# Shield.net
KiCad netlist of a schematic drawn in Altium Designer
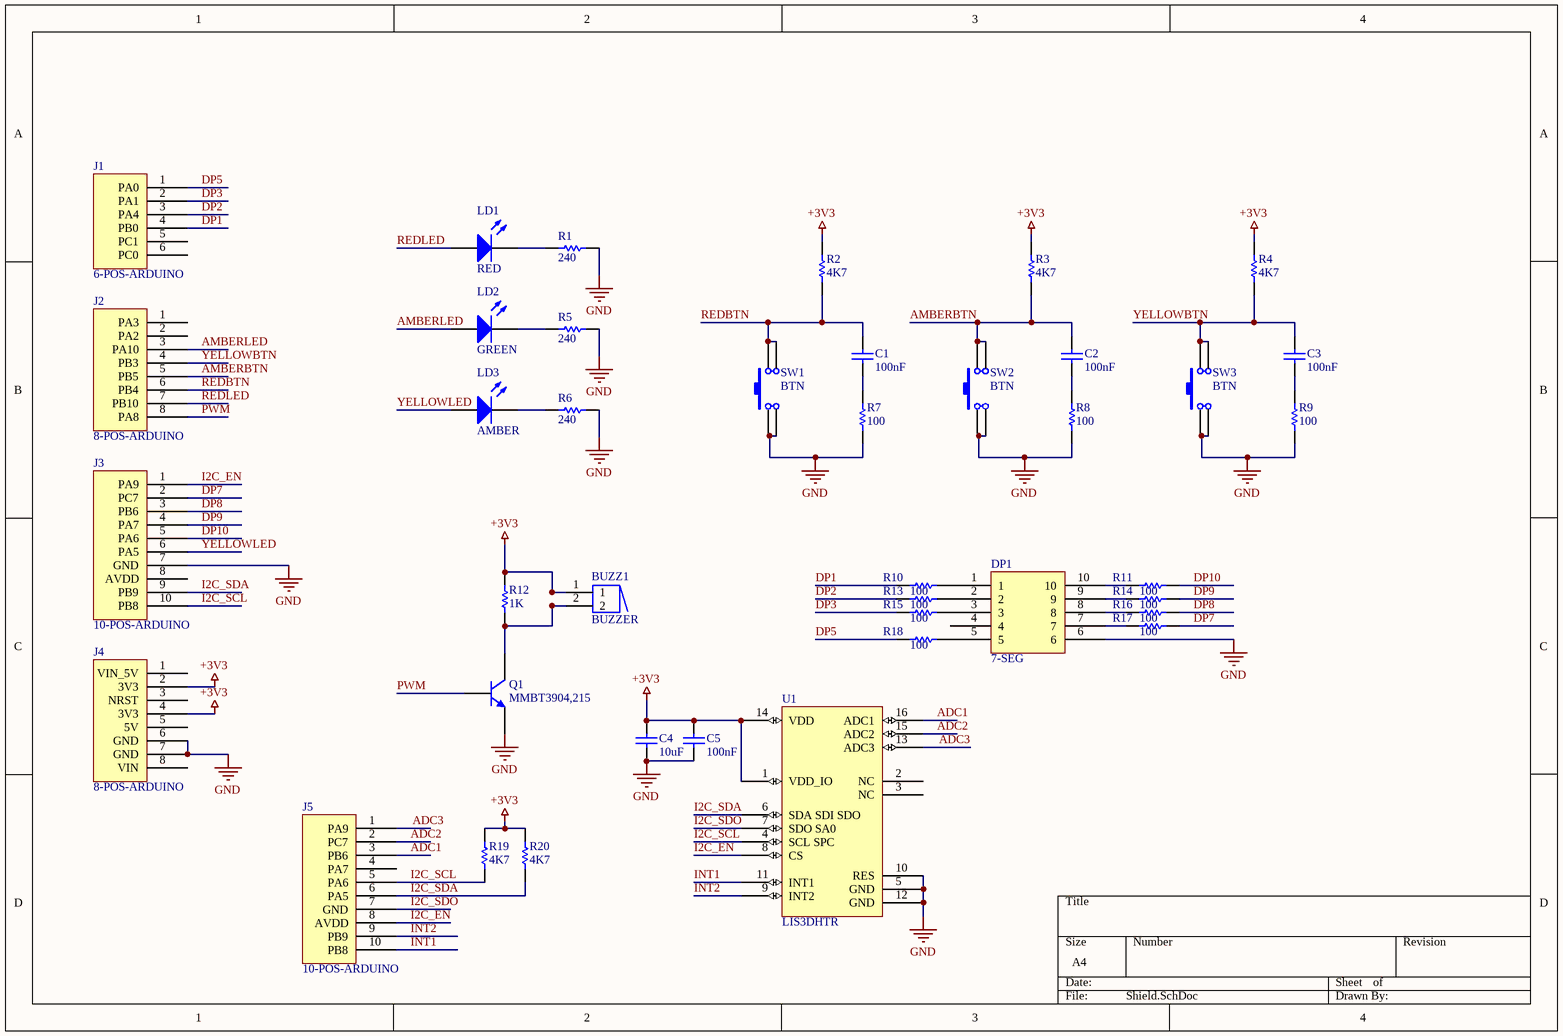
[diagram p0: Shield.SchDoc]

(export (version "E")
  (design (tool "Eeschema 10.0.6"))
  (components
    (comp (ref "BUZZ1")
      (value "BUZZER")
      (footprint "Buzzer")
      (description "AUDIO PIEZO TRANSDUCER 30V TH")
      (fields (field (name "MANUFACTURER") "TDK") (field (name "MANUFACTURER PART NUMBER") "PS1240P02BT"))
      (libsource (lib "Shield") (part "PS1240P02BT"))
    )
    (comp (ref "C1")
      (value "100nF")
      (footprint "CAPC3216X12N")
      (description "CAP CER 0.1UF 50V X7R 1206")
      (fields
        (field (name "MANUFACTURER") "Yageo")
        (field (name "MANUFACTURER PART NUMBER") "CC1206KRX7R9BB104")
      )
      (libsource (lib "Shield") (part "CC1206KRX7R9BB104"))
    )
    (comp (ref "C2")
      (value "100nF")
      (footprint "CAPC3216X12N")
      (description "CAP CER 0.1UF 50V X7R 1206")
      (fields
        (field (name "MANUFACTURER") "Yageo")
        (field (name "MANUFACTURER PART NUMBER") "CC1206KRX7R9BB104")
      )
      (libsource (lib "Shield") (part "CC1206KRX7R9BB104"))
    )
    (comp (ref "C3")
      (value "100nF")
      (footprint "CAPC3216X12N")
      (description "CAP CER 0.1UF 50V X7R 1206")
      (fields
        (field (name "MANUFACTURER") "Yageo")
        (field (name "MANUFACTURER PART NUMBER") "CC1206KRX7R9BB104")
      )
      (libsource (lib "Shield") (part "CC1206KRX7R9BB104"))
    )
    (comp (ref "C4")
      (value "10uF")
      (footprint "CAPC3216X12N")
      (description "Cap Ceramic 10uF 10V X5R 10% SMD 0805 85C Embossed T/R")
      (fields (field (name "TOLERANCE") "10%") (field (name "VOLTAGE") "10V"))
      (libsource (lib "Shield") (part "CL21A106KPFNNNG"))
    )
    (comp (ref "C5")
      (value "100nF")
      (footprint "CAPC3216X12N")
      (description "CAP CER 0.1UF 50V X7R 1206")
      (fields
        (field (name "MANUFACTURER") "Yageo")
        (field (name "MANUFACTURER PART NUMBER") "CC1206KRX7R9BB104")
      )
      (libsource (lib "Shield") (part "CC1206KRX7R9BB104"))
    )
    (comp (ref "DP1")
      (value "7-SEG")
      (footprint "7-seg-display")
      (fields
        (field (name "MANUFACTURER") "Inolux")
        (field (name "MANUFACTURER PART NUMBER") "INND-TS40YGCB")
      )
      (libsource (lib "Shield") (part "INND-TS40YGCB"))
    )
    (comp (ref "J1")
      (value "6-POS-ARDUINO")
      (footprint "PIN 6")
      (description "Conn Header Vert 6POS 2.54MM")
      (fields
        (field (name "MANUFACTURER") "Sullins")
        (field (name "MANUFACTURER PART NUMBER") "PREC006SABN-RC")
      )
      (libsource (lib "Shield") (part "PREC006SABN-RC"))
    )
    (comp (ref "J2")
      (value "8-POS-ARDUINO")
      (footprint "PIN 8")
      (description "CONN HEADER VERT 8POS 2.54MM")
      (fields
        (field (name "MANUFACTURER") "Sullins")
        (field (name "MANUFACTURER PART NUMBER") "PREC008SAAN-RC")
      )
      (libsource (lib "Shield") (part "PREC008SAAN-RC"))
    )
    (comp (ref "J3")
      (value "10-POS-ARDUINO")
      (footprint "PIN 10")
      (description "CONN HEADER .100\" SNGL STR 10POS")
      (fields
        (field (name "MANUFACTURER") "Sullins")
        (field (name "MANUFACTURER PART NUMBER") "PREC010SAAN-RC")
      )
      (libsource (lib "Shield") (part "PREC010SAAN-RC"))
    )
    (comp (ref "J4")
      (value "8-POS-ARDUINO")
      (footprint "PIN 8")
      (description "CONN HEADER VERT 8POS 2.54MM")
      (fields
        (field (name "MANUFACTURER") "Sullins")
        (field (name "MANUFACTURER PART NUMBER") "PREC008SAAN-RC")
      )
      (libsource (lib "Shield") (part "PREC008SAAN-RC (2)"))
    )
    (comp (ref "J5")
      (value "10-POS-ARDUINO")
      (footprint "PIN 10")
      (description "CONN HEADER .100\" SNGL STR 10POS")
      (fields
        (field (name "MANUFACTURER") "Sullins")
        (field (name "MANUFACTURER PART NUMBER") "PREC010SAAN-RC")
      )
      (libsource (lib "Shield") (part "PREC010SAAN-RC"))
    )
    (comp (ref "LD1")
      (value "RED")
      (footprint "DIOC3216X21N")
      (description "LED Uni-Color Red 660nm 2-Pin Chip LED T/R")
      (fields
        (field (name "MANUFACTURER") "Vishay Lite-On")
        (field (name "MANUFACTURER PART NUMBER") "LTST-C150CKT")
      )
      (libsource (lib "Shield") (part "LTST-C150CKT"))
    )
    (comp (ref "LD2")
      (value "GREEN")
      (footprint "DIOC3216X21N")
      (description "LED GREEN CLEAR 1206 SMD")
      (fields
        (field (name "MANUFACTURER") "Vishay Lite-On")
        (field (name "MANUFACTURER PART NUMBER") "LTST-C150GKT")
      )
      (libsource (lib "Shield") (part "LTST-C150GKT"))
    )
    (comp (ref "LD3")
      (value "AMBER")
      (footprint "DIOC3216X21N")
      (description "LED AMBER CLEAR 1206 SMD")
      (fields
        (field (name "MANUFACTURER") "Vishay Lite-On")
        (field (name "MANUFACTURER PART NUMBER") "LTST-C150AKT")
      )
      (libsource (lib "Shield") (part "LTST-C150AKT"))
    )
    (comp (ref "Q1")
      (value "MMBT3904,215")
      (footprint "SOT95P230X110-3N")
      (description "TRANS NPN 40V 0.2A SOT23")
      (fields (field (name "MANUFACTURER") "Nexperia"))
      (libsource (lib "Shield") (part "MMBT3904,215"))
    )
    (comp (ref "R1")
      (value "240")
      (footprint "RESC3115X06N")
      (description "Res Thick Film 1206 240 Ohm 1% 0.25W(1/4W) ±100ppm/C Molded SMD Automotive T/R")
      (fields
        (field (name "MANUFACTURER") "Stackpole Electronics")
        (field (name "MANUFACTURER PART NUMBER") "RMCF1206FT240R")
      )
      (libsource (lib "Shield") (part "RMCF1206FT240R"))
    )
    (comp (ref "R2")
      (value "4K7")
      (footprint "RESC3115X06N")
      (description "RES SMD 4.7K OHM 1% 1/4W 1206")
      (fields
        (field (name "MANUFACTURER") "Stackpole Electronics")
        (field (name "MANUFACTURER PART NUMBER") "RMCF1206FT4K70")
      )
      (libsource (lib "Shield") (part "RMCF1206FT4K70"))
    )
    (comp (ref "R3")
      (value "4K7")
      (footprint "RESC3115X06N")
      (description "RES SMD 4.7K OHM 1% 1/4W 1206")
      (fields
        (field (name "MANUFACTURER") "Stackpole Electronics")
        (field (name "MANUFACTURER PART NUMBER") "RMCF1206FT4K70")
      )
      (libsource (lib "Shield") (part "RMCF1206FT4K70"))
    )
    (comp (ref "R4")
      (value "4K7")
      (footprint "RESC3115X06N")
      (description "RES SMD 4.7K OHM 1% 1/4W 1206")
      (fields
        (field (name "MANUFACTURER") "Stackpole Electronics")
        (field (name "MANUFACTURER PART NUMBER") "RMCF1206FT4K70")
      )
      (libsource (lib "Shield") (part "RMCF1206FT4K70"))
    )
    (comp (ref "R5")
      (value "240")
      (footprint "RESC3115X06N")
      (description "Res Thick Film 1206 240 Ohm 1% 0.25W(1/4W) ±100ppm/C Molded SMD Automotive T/R")
      (fields
        (field (name "MANUFACTURER") "Stackpole Electronics")
        (field (name "MANUFACTURER PART NUMBER") "RMCF1206FT240R")
      )
      (libsource (lib "Shield") (part "RMCF1206FT240R"))
    )
    (comp (ref "R6")
      (value "240")
      (footprint "RESC3115X06N")
      (description "Res Thick Film 1206 240 Ohm 1% 0.25W(1/4W) ±100ppm/C Molded SMD Automotive T/R")
      (fields
        (field (name "MANUFACTURER") "Stackpole Electronics")
        (field (name "MANUFACTURER PART NUMBER") "RMCF1206FT240R")
      )
      (libsource (lib "Shield") (part "RMCF1206FT240R"))
    )
    (comp (ref "R7")
      (value "100")
      (footprint "RESC3115X06N")
      (description "RES 100 OHM 1% 1/4W 1206")
      (fields
        (field (name "MANUFACTURER") "Stackpole Electronics")
        (field (name "MANUFACTURER PART NUMBER") "RMCF1206FT100R")
      )
      (libsource (lib "Shield") (part "RMCF1206FT100R"))
    )
    (comp (ref "R8")
      (value "100")
      (footprint "RESC3115X06N")
      (description "RES 100 OHM 1% 1/4W 1206")
      (fields
        (field (name "MANUFACTURER") "Stackpole Electronics")
        (field (name "MANUFACTURER PART NUMBER") "RMCF1206FT100R")
      )
      (libsource (lib "Shield") (part "RMCF1206FT100R"))
    )
    (comp (ref "R9")
      (value "100")
      (footprint "RESC3115X06N")
      (description "RES 100 OHM 1% 1/4W 1206")
      (fields
        (field (name "MANUFACTURER") "Stackpole Electronics")
        (field (name "MANUFACTURER PART NUMBER") "RMCF1206FT100R")
      )
      (libsource (lib "Shield") (part "RMCF1206FT100R"))
    )
    (comp (ref "R10")
      (value "100")
      (footprint "RESC3115X06N")
      (description "RES 100 OHM 1% 1/4W 1206")
      (fields
        (field (name "MANUFACTURER") "Stackpole Electronics")
        (field (name "MANUFACTURER PART NUMBER") "RMCF1206FT100R")
      )
      (libsource (lib "Shield") (part "RMCF1206FT100R"))
    )
    (comp (ref "R11")
      (value "100")
      (footprint "RESC3115X06N")
      (description "RES 100 OHM 1% 1/4W 1206")
      (fields
        (field (name "MANUFACTURER") "Stackpole Electronics")
        (field (name "MANUFACTURER PART NUMBER") "RMCF1206FT100R")
      )
      (libsource (lib "Shield") (part "RMCF1206FT100R"))
    )
    (comp (ref "R12")
      (value "1K")
      (footprint "RESC3115X06N")
      (description "RES 1K OHM 1% 1/2W 1206")
      (fields
        (field (name "MANUFACTURER") "Stackpole Electronics")
        (field (name "MANUFACTURER PART NUMBER") "RNCP1206FTD1K00")
      )
      (libsource (lib "Shield") (part "RNCP1206FTD1K00"))
    )
    (comp (ref "R13")
      (value "100")
      (footprint "RESC3115X06N")
      (description "RES 100 OHM 1% 1/4W 1206")
      (fields
        (field (name "MANUFACTURER") "Stackpole Electronics")
        (field (name "MANUFACTURER PART NUMBER") "RMCF1206FT100R")
      )
      (libsource (lib "Shield") (part "RMCF1206FT100R"))
    )
    (comp (ref "R14")
      (value "100")
      (footprint "RESC3115X06N")
      (description "RES 100 OHM 1% 1/4W 1206")
      (fields
        (field (name "MANUFACTURER") "Stackpole Electronics")
        (field (name "MANUFACTURER PART NUMBER") "RMCF1206FT100R")
      )
      (libsource (lib "Shield") (part "RMCF1206FT100R"))
    )
    (comp (ref "R15")
      (value "100")
      (footprint "RESC3115X06N")
      (description "RES 100 OHM 1% 1/4W 1206")
      (fields
        (field (name "MANUFACTURER") "Stackpole Electronics")
        (field (name "MANUFACTURER PART NUMBER") "RMCF1206FT100R")
      )
      (libsource (lib "Shield") (part "RMCF1206FT100R"))
    )
    (comp (ref "R16")
      (value "100")
      (footprint "RESC3115X06N")
      (description "RES 100 OHM 1% 1/4W 1206")
      (fields
        (field (name "MANUFACTURER") "Stackpole Electronics")
        (field (name "MANUFACTURER PART NUMBER") "RMCF1206FT100R")
      )
      (libsource (lib "Shield") (part "RMCF1206FT100R"))
    )
    (comp (ref "R17")
      (value "100")
      (footprint "RESC3115X06N")
      (description "RES 100 OHM 1% 1/4W 1206")
      (fields
        (field (name "MANUFACTURER") "Stackpole Electronics")
        (field (name "MANUFACTURER PART NUMBER") "RMCF1206FT100R")
      )
      (libsource (lib "Shield") (part "RMCF1206FT100R"))
    )
    (comp (ref "R18")
      (value "100")
      (footprint "RESC3115X06N")
      (description "RES 100 OHM 1% 1/4W 1206")
      (fields
        (field (name "MANUFACTURER") "Stackpole Electronics")
        (field (name "MANUFACTURER PART NUMBER") "RMCF1206FT100R")
      )
      (libsource (lib "Shield") (part "RMCF1206FT100R"))
    )
    (comp (ref "R19")
      (value "4K7")
      (footprint "RESC3115X06N")
      (description "RES SMD 4.7K OHM 1% 1/4W 1206")
      (fields
        (field (name "MANUFACTURER") "Stackpole Electronics")
        (field (name "MANUFACTURER PART NUMBER") "RMCF1206FT4K70")
      )
      (libsource (lib "Shield") (part "RMCF1206FT4K70"))
    )
    (comp (ref "R20")
      (value "4K7")
      (footprint "RESC3115X06N")
      (description "RES SMD 4.7K OHM 1% 1/4W 1206")
      (fields
        (field (name "MANUFACTURER") "Stackpole Electronics")
        (field (name "MANUFACTURER PART NUMBER") "RMCF1206FT4K70")
      )
      (libsource (lib "Shield") (part "RMCF1206FT4K70"))
    )
    (comp (ref "SW1")
      (value "BTN")
      (footprint "Button")
      (description "INWALL LENS COVER , WHITE , 6 (")
      (fields
        (field (name "MANUFACTURER") "ITT C&K")
        (field (name "MANUFACTURER PART NUMBER") "PTS647SK70SMTR2LFS")
      )
      (libsource (lib "Shield") (part "PTS647SK70SMTR2LFS"))
    )
    (comp (ref "SW2")
      (value "BTN")
      (footprint "Button")
      (description "INWALL LENS COVER , WHITE , 6 (")
      (fields
        (field (name "MANUFACTURER") "ITT C&K")
        (field (name "MANUFACTURER PART NUMBER") "PTS647SK70SMTR2LFS")
      )
      (libsource (lib "Shield") (part "PTS647SK70SMTR2LFS"))
    )
    (comp (ref "SW3")
      (value "BTN")
      (footprint "Button")
      (description "INWALL LENS COVER , WHITE , 6 (")
      (fields
        (field (name "MANUFACTURER") "ITT C&K")
        (field (name "MANUFACTURER PART NUMBER") "PTS647SK70SMTR2LFS")
      )
      (libsource (lib "Shield") (part "PTS647SK70SMTR2LFS"))
    )
    (comp (ref "U1")
      (value "LIS3DHTR")
      (footprint "LGA16")
      (description "ACCEL 2-16G I2C/SPI 16LGA")
      (libsource (lib "Shield") (part "LIS3DHTR"))
    )
  )
  (nets
    (net (code "1") (name "+3V3") (class "Default")
      (node (ref "BUZZ1") (pin "1") (pinfunction "1_1") (pintype "passive"))
      (node (ref "C4") (pin "2") (pinfunction "2_2") (pintype "passive"))
      (node (ref "C5") (pin "2") (pinfunction "2_2") (pintype "passive"))
      (node (ref "J4") (pin "2") (pinfunction "3V3_2") (pintype "passive"))
      (node (ref "J4") (pin "4") (pinfunction "3V3_4") (pintype "passive"))
      (node (ref "R12") (pin "2") (pinfunction "2_2") (pintype "passive"))
      (node (ref "R19") (pin "2") (pinfunction "2_2") (pintype "passive"))
      (node (ref "R2") (pin "2") (pinfunction "2_2") (pintype "passive"))
      (node (ref "R20") (pin "2") (pinfunction "2_2") (pintype "passive"))
      (node (ref "R3") (pin "2") (pinfunction "2_2") (pintype "passive"))
      (node (ref "R4") (pin "2") (pinfunction "2_2") (pintype "passive"))
      (node (ref "U1") (pin "1") (pinfunction "VDD_IO_1") (pintype "bidirectional"))
      (node (ref "U1") (pin "14") (pinfunction "VDD_14") (pintype "bidirectional"))
    )
    (net (code "2") (name "/ADC1") (class "Default")
      (node (ref "J5") (pin "3") (pinfunction "PB6_3") (pintype "passive"))
      (node (ref "U1") (pin "16") (pinfunction "ADC1_16") (pintype "bidirectional"))
    )
    (net (code "3") (name "/ADC2") (class "Default")
      (node (ref "J5") (pin "2") (pinfunction "PC7_2") (pintype "passive"))
      (node (ref "U1") (pin "15") (pinfunction "ADC2_15") (pintype "bidirectional"))
    )
    (net (code "4") (name "/ADC3") (class "Default")
      (node (ref "J5") (pin "1") (pinfunction "PA9_1") (pintype "passive"))
      (node (ref "U1") (pin "13") (pinfunction "ADC3_13") (pintype "bidirectional"))
    )
    (net (code "5") (name "/AMBERBTN") (class "Default")
      (node (ref "C2") (pin "2") (pinfunction "2_2") (pintype "passive"))
      (node (ref "J2") (pin "5") (pinfunction "PB5_5") (pintype "passive"))
      (node (ref "R3") (pin "1") (pinfunction "1_1") (pintype "passive"))
      (node (ref "SW2") (pin "3") (pinfunction "2_3") (pintype "passive"))
      (node (ref "SW2") (pin "4") (pinfunction "3_4") (pintype "passive"))
    )
    (net (code "6") (name "/AMBERLED") (class "Default")
      (node (ref "J2") (pin "3") (pinfunction "PA10_3") (pintype "passive"))
      (node (ref "LD2") (pin "1") (pinfunction "A_1") (pintype "passive"))
    )
    (net (code "7") (name "/DP1") (class "Default")
      (node (ref "J1") (pin "4") (pinfunction "PB0_4") (pintype "passive"))
      (node (ref "R10") (pin "2") (pinfunction "2_2") (pintype "passive"))
    )
    (net (code "8") (name "/DP2") (class "Default")
      (node (ref "J1") (pin "3") (pinfunction "PA4_3") (pintype "passive"))
      (node (ref "R13") (pin "2") (pinfunction "2_2") (pintype "passive"))
    )
    (net (code "9") (name "/DP3") (class "Default")
      (node (ref "J1") (pin "2") (pinfunction "PA1_2") (pintype "passive"))
      (node (ref "R15") (pin "2") (pinfunction "2_2") (pintype "passive"))
    )
    (net (code "10") (name "/DP5") (class "Default")
      (node (ref "J1") (pin "1") (pinfunction "PA0_1") (pintype "passive"))
      (node (ref "R18") (pin "2") (pinfunction "2_2") (pintype "passive"))
    )
    (net (code "11") (name "/DP7") (class "Default")
      (node (ref "J3") (pin "2") (pinfunction "PC7_2") (pintype "passive"))
      (node (ref "R17") (pin "1") (pinfunction "1_1") (pintype "passive"))
    )
    (net (code "12") (name "/DP8") (class "Default")
      (node (ref "J3") (pin "3") (pinfunction "PB6_3") (pintype "passive"))
      (node (ref "R16") (pin "1") (pinfunction "1_1") (pintype "passive"))
    )
    (net (code "13") (name "/DP9") (class "Default")
      (node (ref "J3") (pin "4") (pinfunction "PA7_4") (pintype "passive"))
      (node (ref "R14") (pin "1") (pinfunction "1_1") (pintype "passive"))
    )
    (net (code "14") (name "/DP10") (class "Default")
      (node (ref "J3") (pin "5") (pinfunction "PA6_5") (pintype "passive"))
      (node (ref "R11") (pin "1") (pinfunction "1_1") (pintype "passive"))
    )
    (net (code "15") (name "/I2C_EN") (class "Default")
      (node (ref "J3") (pin "1") (pinfunction "PA9_1") (pintype "passive"))
      (node (ref "J5") (pin "8") (pinfunction "AVDD_8") (pintype "passive"))
      (node (ref "U1") (pin "8") (pinfunction "CS_8") (pintype "bidirectional"))
    )
    (net (code "16") (name "/I2C_SCL") (class "Default")
      (node (ref "J3") (pin "10") (pinfunction "PB8_10") (pintype "passive"))
      (node (ref "J5") (pin "5") (pinfunction "PA6_5") (pintype "passive"))
      (node (ref "R19") (pin "1") (pinfunction "1_1") (pintype "passive"))
      (node (ref "U1") (pin "4") (pinfunction "SCL_SPC_4") (pintype "bidirectional"))
    )
    (net (code "17") (name "/I2C_SDA") (class "Default")
      (node (ref "J3") (pin "9") (pinfunction "PB9_9") (pintype "passive"))
      (node (ref "J5") (pin "6") (pinfunction "PA5_6") (pintype "passive"))
      (node (ref "R20") (pin "1") (pinfunction "1_1") (pintype "passive"))
      (node (ref "U1") (pin "6") (pinfunction "SDA_SDI_SDO_6") (pintype "bidirectional"))
    )
    (net (code "18") (name "/I2C_SDO") (class "Default")
      (node (ref "J5") (pin "7") (pinfunction "GND_7") (pintype "passive"))
      (node (ref "U1") (pin "7") (pinfunction "SDO_SA0_7") (pintype "bidirectional"))
    )
    (net (code "19") (name "/INT1") (class "Default")
      (node (ref "J5") (pin "10") (pinfunction "PB8_10") (pintype "passive"))
      (node (ref "U1") (pin "11") (pinfunction "INT1_11") (pintype "bidirectional"))
    )
    (net (code "20") (name "/INT2") (class "Default")
      (node (ref "J5") (pin "9") (pinfunction "PB9_9") (pintype "passive"))
      (node (ref "U1") (pin "9") (pinfunction "INT2_9") (pintype "bidirectional"))
    )
    (net (code "21") (name "/PWM") (class "Default")
      (node (ref "J2") (pin "8") (pinfunction "PA8_8") (pintype "passive"))
      (node (ref "Q1") (pin "1") (pinfunction "B_1") (pintype "passive"))
    )
    (net (code "22") (name "/REDBTN") (class "Default")
      (node (ref "C1") (pin "2") (pinfunction "2_2") (pintype "passive"))
      (node (ref "J2") (pin "6") (pinfunction "PB4_6") (pintype "passive"))
      (node (ref "R2") (pin "1") (pinfunction "1_1") (pintype "passive"))
      (node (ref "SW1") (pin "3") (pinfunction "2_3") (pintype "passive"))
      (node (ref "SW1") (pin "4") (pinfunction "3_4") (pintype "passive"))
    )
    (net (code "23") (name "/REDLED") (class "Default")
      (node (ref "J2") (pin "7") (pinfunction "PB10_7") (pintype "passive"))
      (node (ref "LD1") (pin "1") (pinfunction "A_1") (pintype "passive"))
    )
    (net (code "24") (name "/YELLOWBTN") (class "Default")
      (node (ref "C3") (pin "2") (pinfunction "2_2") (pintype "passive"))
      (node (ref "J2") (pin "4") (pinfunction "PB3_4") (pintype "passive"))
      (node (ref "R4") (pin "1") (pinfunction "1_1") (pintype "passive"))
      (node (ref "SW3") (pin "3") (pinfunction "2_3") (pintype "passive"))
      (node (ref "SW3") (pin "4") (pinfunction "3_4") (pintype "passive"))
    )
    (net (code "25") (name "/YELLOWLED") (class "Default")
      (node (ref "J3") (pin "6") (pinfunction "PA5_6") (pintype "passive"))
      (node (ref "LD3") (pin "1") (pinfunction "A_1") (pintype "passive"))
    )
    (net (code "26") (name "GND") (class "Default")
      (node (ref "C4") (pin "1") (pinfunction "1_1") (pintype "passive"))
      (node (ref "C5") (pin "1") (pinfunction "1_1") (pintype "passive"))
      (node (ref "DP1") (pin "6") (pinfunction "6_6") (pintype "passive"))
      (node (ref "J3") (pin "7") (pinfunction "GND_7") (pintype "passive"))
      (node (ref "J4") (pin "6") (pinfunction "GND_6") (pintype "passive"))
      (node (ref "J4") (pin "7") (pinfunction "GND_7") (pintype "passive"))
      (node (ref "Q1") (pin "2") (pinfunction "E_2") (pintype "passive"))
      (node (ref "R1") (pin "2") (pinfunction "2_2") (pintype "passive"))
      (node (ref "R5") (pin "2") (pinfunction "2_2") (pintype "passive"))
      (node (ref "R6") (pin "2") (pinfunction "2_2") (pintype "passive"))
      (node (ref "R7") (pin "1") (pinfunction "1_1") (pintype "passive"))
      (node (ref "R8") (pin "1") (pinfunction "1_1") (pintype "passive"))
      (node (ref "R9") (pin "1") (pinfunction "1_1") (pintype "passive"))
      (node (ref "SW1") (pin "1") (pinfunction "1_1") (pintype "passive"))
      (node (ref "SW1") (pin "2") (pinfunction "1_2") (pintype "passive"))
      (node (ref "SW2") (pin "1") (pinfunction "1_1") (pintype "passive"))
      (node (ref "SW2") (pin "2") (pinfunction "1_2") (pintype "passive"))
      (node (ref "SW3") (pin "1") (pinfunction "1_1") (pintype "passive"))
      (node (ref "SW3") (pin "2") (pinfunction "1_2") (pintype "passive"))
      (node (ref "U1") (pin "10") (pinfunction "RES_10") (pintype "power_in"))
      (node (ref "U1") (pin "12") (pinfunction "GND_12") (pintype "power_in"))
      (node (ref "U1") (pin "5") (pinfunction "GND_5") (pintype "power_in"))
    )
    (net (code "27") (name "Net-(C1-Pad1)") (class "Default")
      (node (ref "C1") (pin "1") (pinfunction "1_1") (pintype "passive"))
      (node (ref "R7") (pin "2") (pinfunction "2_2") (pintype "passive"))
    )
    (net (code "28") (name "Net-(C2-Pad1)") (class "Default")
      (node (ref "C2") (pin "1") (pinfunction "1_1") (pintype "passive"))
      (node (ref "R8") (pin "2") (pinfunction "2_2") (pintype "passive"))
    )
    (net (code "29") (name "Net-(C3-Pad1)") (class "Default")
      (node (ref "C3") (pin "1") (pinfunction "1_1") (pintype "passive"))
      (node (ref "R9") (pin "2") (pinfunction "2_2") (pintype "passive"))
    )
    (net (code "30") (name "Net-(DP1-Pad1)") (class "Default")
      (node (ref "DP1") (pin "1") (pinfunction "1_1") (pintype "passive"))
      (node (ref "R10") (pin "1") (pinfunction "1_1") (pintype "passive"))
    )
    (net (code "31") (name "Net-(DP1-Pad2)") (class "Default")
      (node (ref "DP1") (pin "2") (pinfunction "2_2") (pintype "passive"))
      (node (ref "R13") (pin "1") (pinfunction "1_1") (pintype "passive"))
    )
    (net (code "32") (name "Net-(DP1-Pad3)") (class "Default")
      (node (ref "DP1") (pin "3") (pinfunction "3_3") (pintype "passive"))
      (node (ref "R15") (pin "1") (pinfunction "1_1") (pintype "passive"))
    )
    (net (code "33") (name "Net-(DP1-Pad5)") (class "Default")
      (node (ref "DP1") (pin "5") (pinfunction "5_5") (pintype "passive"))
      (node (ref "R18") (pin "1") (pinfunction "1_1") (pintype "passive"))
    )
    (net (code "34") (name "Net-(DP1-Pad7)") (class "Default")
      (node (ref "DP1") (pin "7") (pinfunction "7_7") (pintype "passive"))
      (node (ref "R17") (pin "2") (pinfunction "2_2") (pintype "passive"))
    )
    (net (code "35") (name "Net-(DP1-Pad8)") (class "Default")
      (node (ref "DP1") (pin "8") (pinfunction "8_8") (pintype "passive"))
      (node (ref "R16") (pin "2") (pinfunction "2_2") (pintype "passive"))
    )
    (net (code "36") (name "Net-(DP1-Pad9)") (class "Default")
      (node (ref "DP1") (pin "9") (pinfunction "9_9") (pintype "passive"))
      (node (ref "R14") (pin "2") (pinfunction "2_2") (pintype "passive"))
    )
    (net (code "37") (name "Net-(DP1-Pad10)") (class "Default")
      (node (ref "DP1") (pin "10") (pinfunction "10_10") (pintype "passive"))
      (node (ref "R11") (pin "2") (pinfunction "2_2") (pintype "passive"))
    )
    (net (code "38") (name "Net-(LD1-K)") (class "Default")
      (node (ref "LD1") (pin "2") (pinfunction "K_2") (pintype "passive"))
      (node (ref "R1") (pin "1") (pinfunction "1_1") (pintype "passive"))
    )
    (net (code "39") (name "Net-(LD2-K)") (class "Default")
      (node (ref "LD2") (pin "2") (pinfunction "K_2") (pintype "passive"))
      (node (ref "R5") (pin "1") (pinfunction "1_1") (pintype "passive"))
    )
    (net (code "40") (name "Net-(LD3-K)") (class "Default")
      (node (ref "LD3") (pin "2") (pinfunction "K_2") (pintype "passive"))
      (node (ref "R6") (pin "1") (pinfunction "1_1") (pintype "passive"))
    )
    (net (code "41") (name "Net-(Q1-C)") (class "Default")
      (node (ref "BUZZ1") (pin "2") (pinfunction "2_2") (pintype "passive"))
      (node (ref "Q1") (pin "3") (pinfunction "C_3") (pintype "passive"))
      (node (ref "R12") (pin "1") (pinfunction "1_1") (pintype "passive"))
    )
    (net (code "42") (name "unconnected-(DP1-Pad4)") (class "Default")
      (node (ref "DP1") (pin "4") (pinfunction "4_4") (pintype "passive"))
    )
    (net (code "43") (name "unconnected-(J1-PC0-Pad6)") (class "Default")
      (node (ref "J1") (pin "6") (pinfunction "PC0_6") (pintype "passive"))
    )
    (net (code "44") (name "unconnected-(J1-PC1-Pad5)") (class "Default")
      (node (ref "J1") (pin "5") (pinfunction "PC1_5") (pintype "passive"))
    )
    (net (code "45") (name "unconnected-(J2-PA2-Pad2)") (class "Default")
      (node (ref "J2") (pin "2") (pinfunction "PA2_2") (pintype "passive"))
    )
    (net (code "46") (name "unconnected-(J2-PA3-Pad1)") (class "Default")
      (node (ref "J2") (pin "1") (pinfunction "PA3_1") (pintype "passive"))
    )
    (net (code "47") (name "unconnected-(J3-AVDD-Pad8)") (class "Default")
      (node (ref "J3") (pin "8") (pinfunction "AVDD_8") (pintype "passive"))
    )
    (net (code "48") (name "unconnected-(J4-5V-Pad5)") (class "Default")
      (node (ref "J4") (pin "5") (pinfunction "5V_5") (pintype "passive"))
    )
    (net (code "49") (name "unconnected-(J4-NRST-Pad3)") (class "Default")
      (node (ref "J4") (pin "3") (pinfunction "NRST_3") (pintype "passive"))
    )
    (net (code "50") (name "unconnected-(J4-VIN-Pad8)") (class "Default")
      (node (ref "J4") (pin "8") (pinfunction "VIN_8") (pintype "passive"))
    )
    (net (code "51") (name "unconnected-(J4-VIN_5V-Pad1)") (class "Default")
      (node (ref "J4") (pin "1") (pinfunction "VIN_5V_1") (pintype "passive"))
    )
    (net (code "52") (name "unconnected-(J5-PA7-Pad4)") (class "Default")
      (node (ref "J5") (pin "4") (pinfunction "PA7_4") (pintype "passive"))
    )
    (net (code "53") (name "unconnected-(U1-NC-Pad2)") (class "Default")
      (node (ref "U1") (pin "2") (pinfunction "NC_2") (pintype "passive"))
    )
    (net (code "54") (name "unconnected-(U1-NC-Pad3)") (class "Default")
      (node (ref "U1") (pin "3") (pinfunction "NC_3") (pintype "passive"))
    )
  )
)
